# NandFlash.net
KiCad netlist of a schematic drawn in Altium Designer
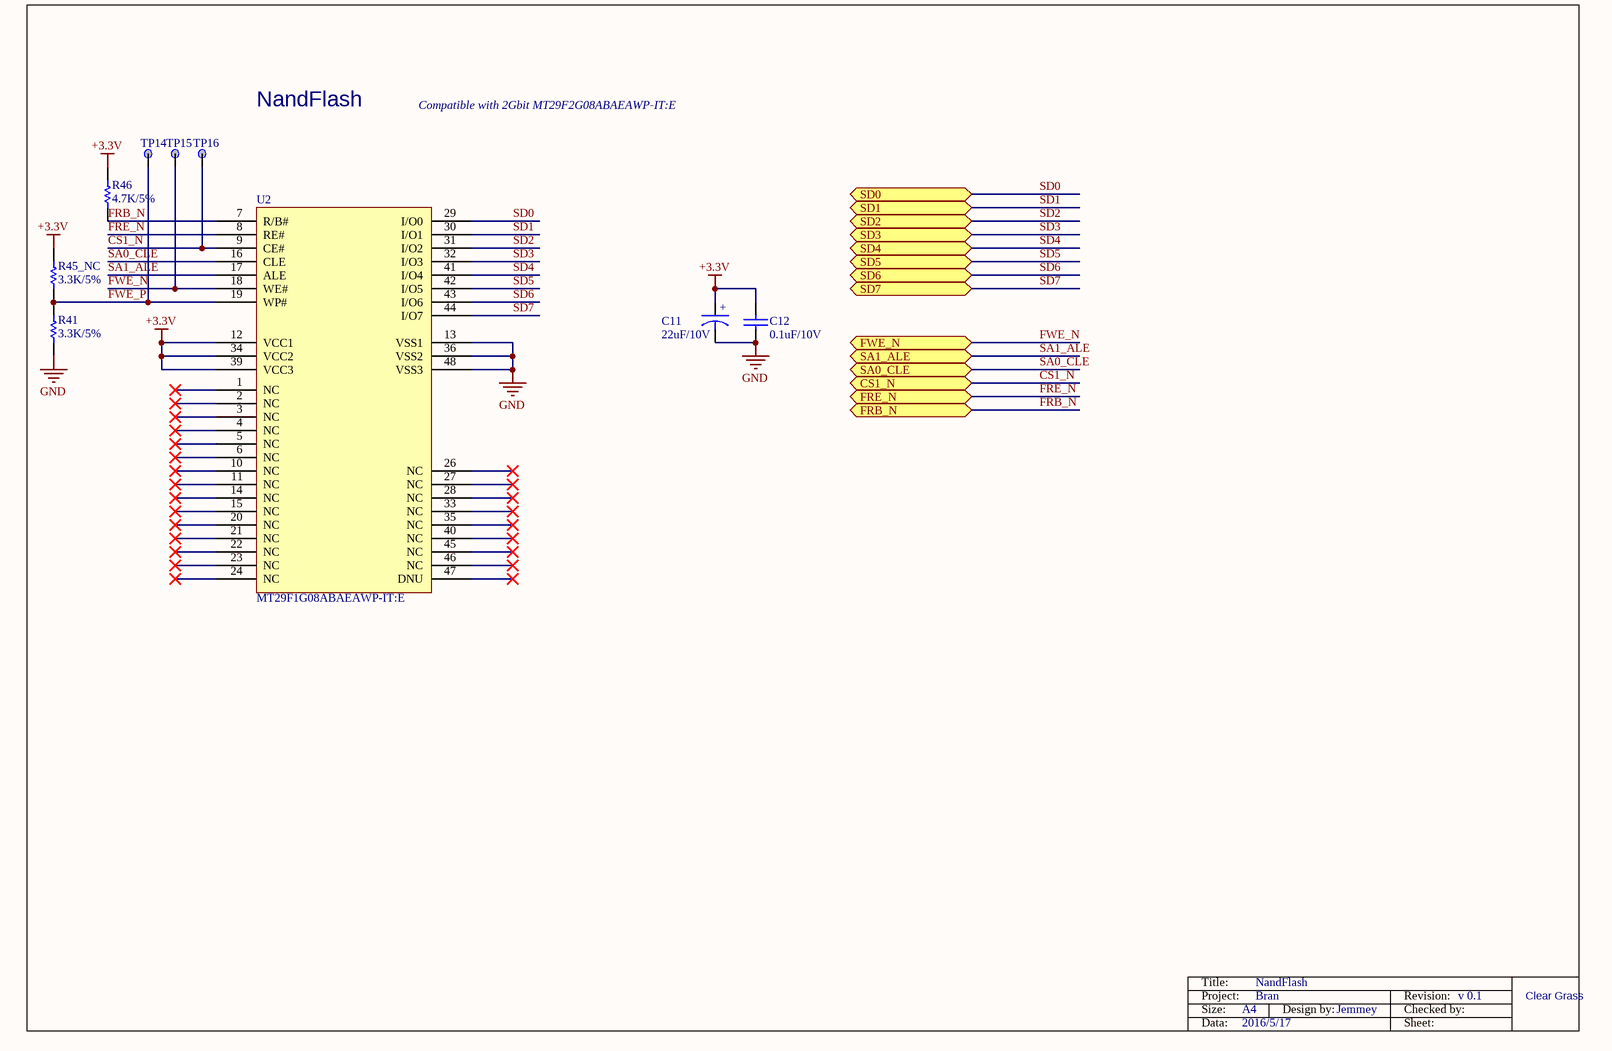
[diagram p0: NandFlash.SchDoc]

(export (version "E")
  (design (tool "Eeschema 10.0.6"))
  (components
    (comp (ref "C11") (value "22uF/10V") (footprint "6032") (libsource (lib "MoJi LIB") (part "Capacitor")))
    (comp (ref "C12")
      (value "0.1uF/10V")
      (footprint "0402C")
      (description "厂家：Murata，型号：GRM155R71A104KA01D")
      (libsource (lib "Amber") (part "CAP"))
    )
    (comp (ref "R41")
      (value "3.3K/5%")
      (footprint "0603R")
      (description "Resistor")
      (fields (field (name "PUBLISHER") "Altium Limited"))
      (libsource (lib "Miscellaneous Devices") (part "Res1"))
    )
    (comp (ref "R45_NC")
      (value "3.3K/5%")
      (footprint "0603R")
      (description "Resistor")
      (fields (field (name "PUBLISHER") "Altium Limited"))
      (libsource (lib "Miscellaneous Devices") (part "Res1"))
    )
    (comp (ref "R46")
      (value "4.7K/5%")
      (footprint "0603R")
      (description "Resistor")
      (fields (field (name "PUBLISHER") "Altium Limited"))
      (libsource (lib "Miscellaneous Devices") (part "Res1"))
    )
    (comp (ref "TP14") (value "TP") (footprint "TP_C40") (libsource (lib "Almos") (part "TP")))
    (comp (ref "TP15") (value "TP") (footprint "TP_C40") (libsource (lib "Almos") (part "TP")))
    (comp (ref "TP16") (value "TP") (footprint "TP_C40") (libsource (lib "Almos") (part "TP")))
    (comp (ref "U2") (value "MT29F1G08ABAEAWP-IT:E") (libsource (lib "Bran MB") (part "NandFlash")))
  )
  (nets
    (net (code "1") (name "+3.3V") (class "Default")
      (node (ref "C11") (pin "1") (pinfunction "1_1") (pintype "passive"))
      (node (ref "C12") (pin "2") (pinfunction "2_2") (pintype "passive"))
      (node (ref "R45_NC") (pin "1") (pinfunction "1_1") (pintype "passive"))
      (node (ref "R46") (pin "1") (pinfunction "1_1") (pintype "passive"))
      (node (ref "U2") (pin "12") (pinfunction "VCC1_12") (pintype "power_in"))
      (node (ref "U2") (pin "34") (pinfunction "VCC2_34") (pintype "power_in"))
      (node (ref "U2") (pin "39") (pinfunction "VCC3_39") (pintype "power_in"))
    )
    (net (code "2") (name "/CS1_N") (class "Default")
      (node (ref "TP16") (pin "1") (pinfunction "1_1") (pintype "passive"))
      (node (ref "U2") (pin "9") (pinfunction "CE#_9") (pintype "power_in"))
    )
    (net (code "3") (name "/FRB_N") (class "Default")
      (node (ref "R46") (pin "2") (pinfunction "2_2") (pintype "passive"))
      (node (ref "U2") (pin "7") (pinfunction "R/B#_7") (pintype "power_in"))
    )
    (net (code "4") (name "/FRE_N") (class "Default")
      (node (ref "U2") (pin "8") (pinfunction "RE#_8") (pintype "power_in"))
    )
    (net (code "5") (name "/FWE_N") (class "Default")
      (node (ref "TP15") (pin "1") (pinfunction "1_1") (pintype "passive"))
      (node (ref "U2") (pin "18") (pinfunction "WE#_18") (pintype "power_in"))
    )
    (net (code "6") (name "/FWE_P") (class "Default")
      (node (ref "R41") (pin "1") (pinfunction "1_1") (pintype "passive"))
      (node (ref "R45_NC") (pin "2") (pinfunction "2_2") (pintype "passive"))
      (node (ref "TP14") (pin "1") (pinfunction "1_1") (pintype "passive"))
      (node (ref "U2") (pin "19") (pinfunction "WP#_19") (pintype "power_in"))
    )
    (net (code "7") (name "/SA0_CLE") (class "Default")
      (node (ref "U2") (pin "16") (pinfunction "CLE_16") (pintype "power_in"))
    )
    (net (code "8") (name "/SA1_ALE") (class "Default")
      (node (ref "U2") (pin "17") (pinfunction "ALE_17") (pintype "power_in"))
    )
    (net (code "9") (name "/SD0") (class "Default")
      (node (ref "U2") (pin "29") (pinfunction "I/O0_29") (pintype "power_in"))
    )
    (net (code "10") (name "/SD1") (class "Default")
      (node (ref "U2") (pin "30") (pinfunction "I/O1_30") (pintype "power_in"))
    )
    (net (code "11") (name "/SD2") (class "Default")
      (node (ref "U2") (pin "31") (pinfunction "I/O2_31") (pintype "power_in"))
    )
    (net (code "12") (name "/SD3") (class "Default")
      (node (ref "U2") (pin "32") (pinfunction "I/O3_32") (pintype "power_in"))
    )
    (net (code "13") (name "/SD4") (class "Default")
      (node (ref "U2") (pin "41") (pinfunction "I/O4_41") (pintype "power_in"))
    )
    (net (code "14") (name "/SD5") (class "Default")
      (node (ref "U2") (pin "42") (pinfunction "I/O5_42") (pintype "power_in"))
    )
    (net (code "15") (name "/SD6") (class "Default")
      (node (ref "U2") (pin "43") (pinfunction "I/O6_43") (pintype "power_in"))
    )
    (net (code "16") (name "/SD7") (class "Default")
      (node (ref "U2") (pin "44") (pinfunction "I/O7_44") (pintype "power_in"))
    )
    (net (code "17") (name "GND") (class "Default")
      (node (ref "C11") (pin "2") (pinfunction "2_2") (pintype "passive"))
      (node (ref "C12") (pin "1") (pinfunction "1_1") (pintype "passive"))
      (node (ref "R41") (pin "2") (pinfunction "2_2") (pintype "passive"))
      (node (ref "U2") (pin "13") (pinfunction "VSS1_13") (pintype "power_in"))
      (node (ref "U2") (pin "36") (pinfunction "VSS2_36") (pintype "power_in"))
      (node (ref "U2") (pin "48") (pinfunction "VSS3_48") (pintype "power_in"))
    )
    (net (code "18") (name "unconnected-(U2-DNU-Pad47)") (class "Default")
      (node (ref "U2") (pin "47") (pinfunction "DNU_47") (pintype "power_in+no_connect"))
    )
    (net (code "19") (name "unconnected-(U2-NC-Pad1)") (class "Default")
      (node (ref "U2") (pin "1") (pinfunction "NC_1") (pintype "power_in+no_connect"))
    )
    (net (code "20") (name "unconnected-(U2-NC-Pad2)") (class "Default")
      (node (ref "U2") (pin "2") (pinfunction "NC_2") (pintype "power_in+no_connect"))
    )
    (net (code "21") (name "unconnected-(U2-NC-Pad3)") (class "Default")
      (node (ref "U2") (pin "3") (pinfunction "NC_3") (pintype "power_in+no_connect"))
    )
    (net (code "22") (name "unconnected-(U2-NC-Pad4)") (class "Default")
      (node (ref "U2") (pin "4") (pinfunction "NC_4") (pintype "power_in+no_connect"))
    )
    (net (code "23") (name "unconnected-(U2-NC-Pad5)") (class "Default")
      (node (ref "U2") (pin "5") (pinfunction "NC_5") (pintype "power_in+no_connect"))
    )
    (net (code "24") (name "unconnected-(U2-NC-Pad6)") (class "Default")
      (node (ref "U2") (pin "6") (pinfunction "NC_6") (pintype "power_in+no_connect"))
    )
    (net (code "25") (name "unconnected-(U2-NC-Pad10)") (class "Default")
      (node (ref "U2") (pin "10") (pinfunction "NC_10") (pintype "power_in+no_connect"))
    )
    (net (code "26") (name "unconnected-(U2-NC-Pad11)") (class "Default")
      (node (ref "U2") (pin "11") (pinfunction "NC_11") (pintype "power_in+no_connect"))
    )
    (net (code "27") (name "unconnected-(U2-NC-Pad14)") (class "Default")
      (node (ref "U2") (pin "14") (pinfunction "NC_14") (pintype "power_in+no_connect"))
    )
    (net (code "28") (name "unconnected-(U2-NC-Pad15)") (class "Default")
      (node (ref "U2") (pin "15") (pinfunction "NC_15") (pintype "power_in+no_connect"))
    )
    (net (code "29") (name "unconnected-(U2-NC-Pad20)") (class "Default")
      (node (ref "U2") (pin "20") (pinfunction "NC_20") (pintype "power_in+no_connect"))
    )
    (net (code "30") (name "unconnected-(U2-NC-Pad21)") (class "Default")
      (node (ref "U2") (pin "21") (pinfunction "NC_21") (pintype "power_in+no_connect"))
    )
    (net (code "31") (name "unconnected-(U2-NC-Pad22)") (class "Default")
      (node (ref "U2") (pin "22") (pinfunction "NC_22") (pintype "power_in+no_connect"))
    )
    (net (code "32") (name "unconnected-(U2-NC-Pad23)") (class "Default")
      (node (ref "U2") (pin "23") (pinfunction "NC_23") (pintype "power_in+no_connect"))
    )
    (net (code "33") (name "unconnected-(U2-NC-Pad24)") (class "Default")
      (node (ref "U2") (pin "24") (pinfunction "NC_24") (pintype "power_in+no_connect"))
    )
    (net (code "34") (name "unconnected-(U2-NC-Pad26)") (class "Default")
      (node (ref "U2") (pin "26") (pinfunction "NC_26") (pintype "power_in+no_connect"))
    )
    (net (code "35") (name "unconnected-(U2-NC-Pad27)") (class "Default")
      (node (ref "U2") (pin "27") (pinfunction "NC_27") (pintype "power_in+no_connect"))
    )
    (net (code "36") (name "unconnected-(U2-NC-Pad28)") (class "Default")
      (node (ref "U2") (pin "28") (pinfunction "NC_28") (pintype "power_in+no_connect"))
    )
    (net (code "37") (name "unconnected-(U2-NC-Pad33)") (class "Default")
      (node (ref "U2") (pin "33") (pinfunction "NC_33") (pintype "power_in+no_connect"))
    )
    (net (code "38") (name "unconnected-(U2-NC-Pad35)") (class "Default")
      (node (ref "U2") (pin "35") (pinfunction "NC_35") (pintype "power_in+no_connect"))
    )
    (net (code "39") (name "unconnected-(U2-NC-Pad40)") (class "Default")
      (node (ref "U2") (pin "40") (pinfunction "NC_40") (pintype "power_in+no_connect"))
    )
    (net (code "40") (name "unconnected-(U2-NC-Pad45)") (class "Default")
      (node (ref "U2") (pin "45") (pinfunction "NC_45") (pintype "power_in+no_connect"))
    )
    (net (code "41") (name "unconnected-(U2-NC-Pad46)") (class "Default")
      (node (ref "U2") (pin "46") (pinfunction "NC_46") (pintype "power_in+no_connect"))
    )
  )
)
